# 3_Cambridge_Measurement_TOP.net
KiCad netlist of a schematic drawn in Altium Designer
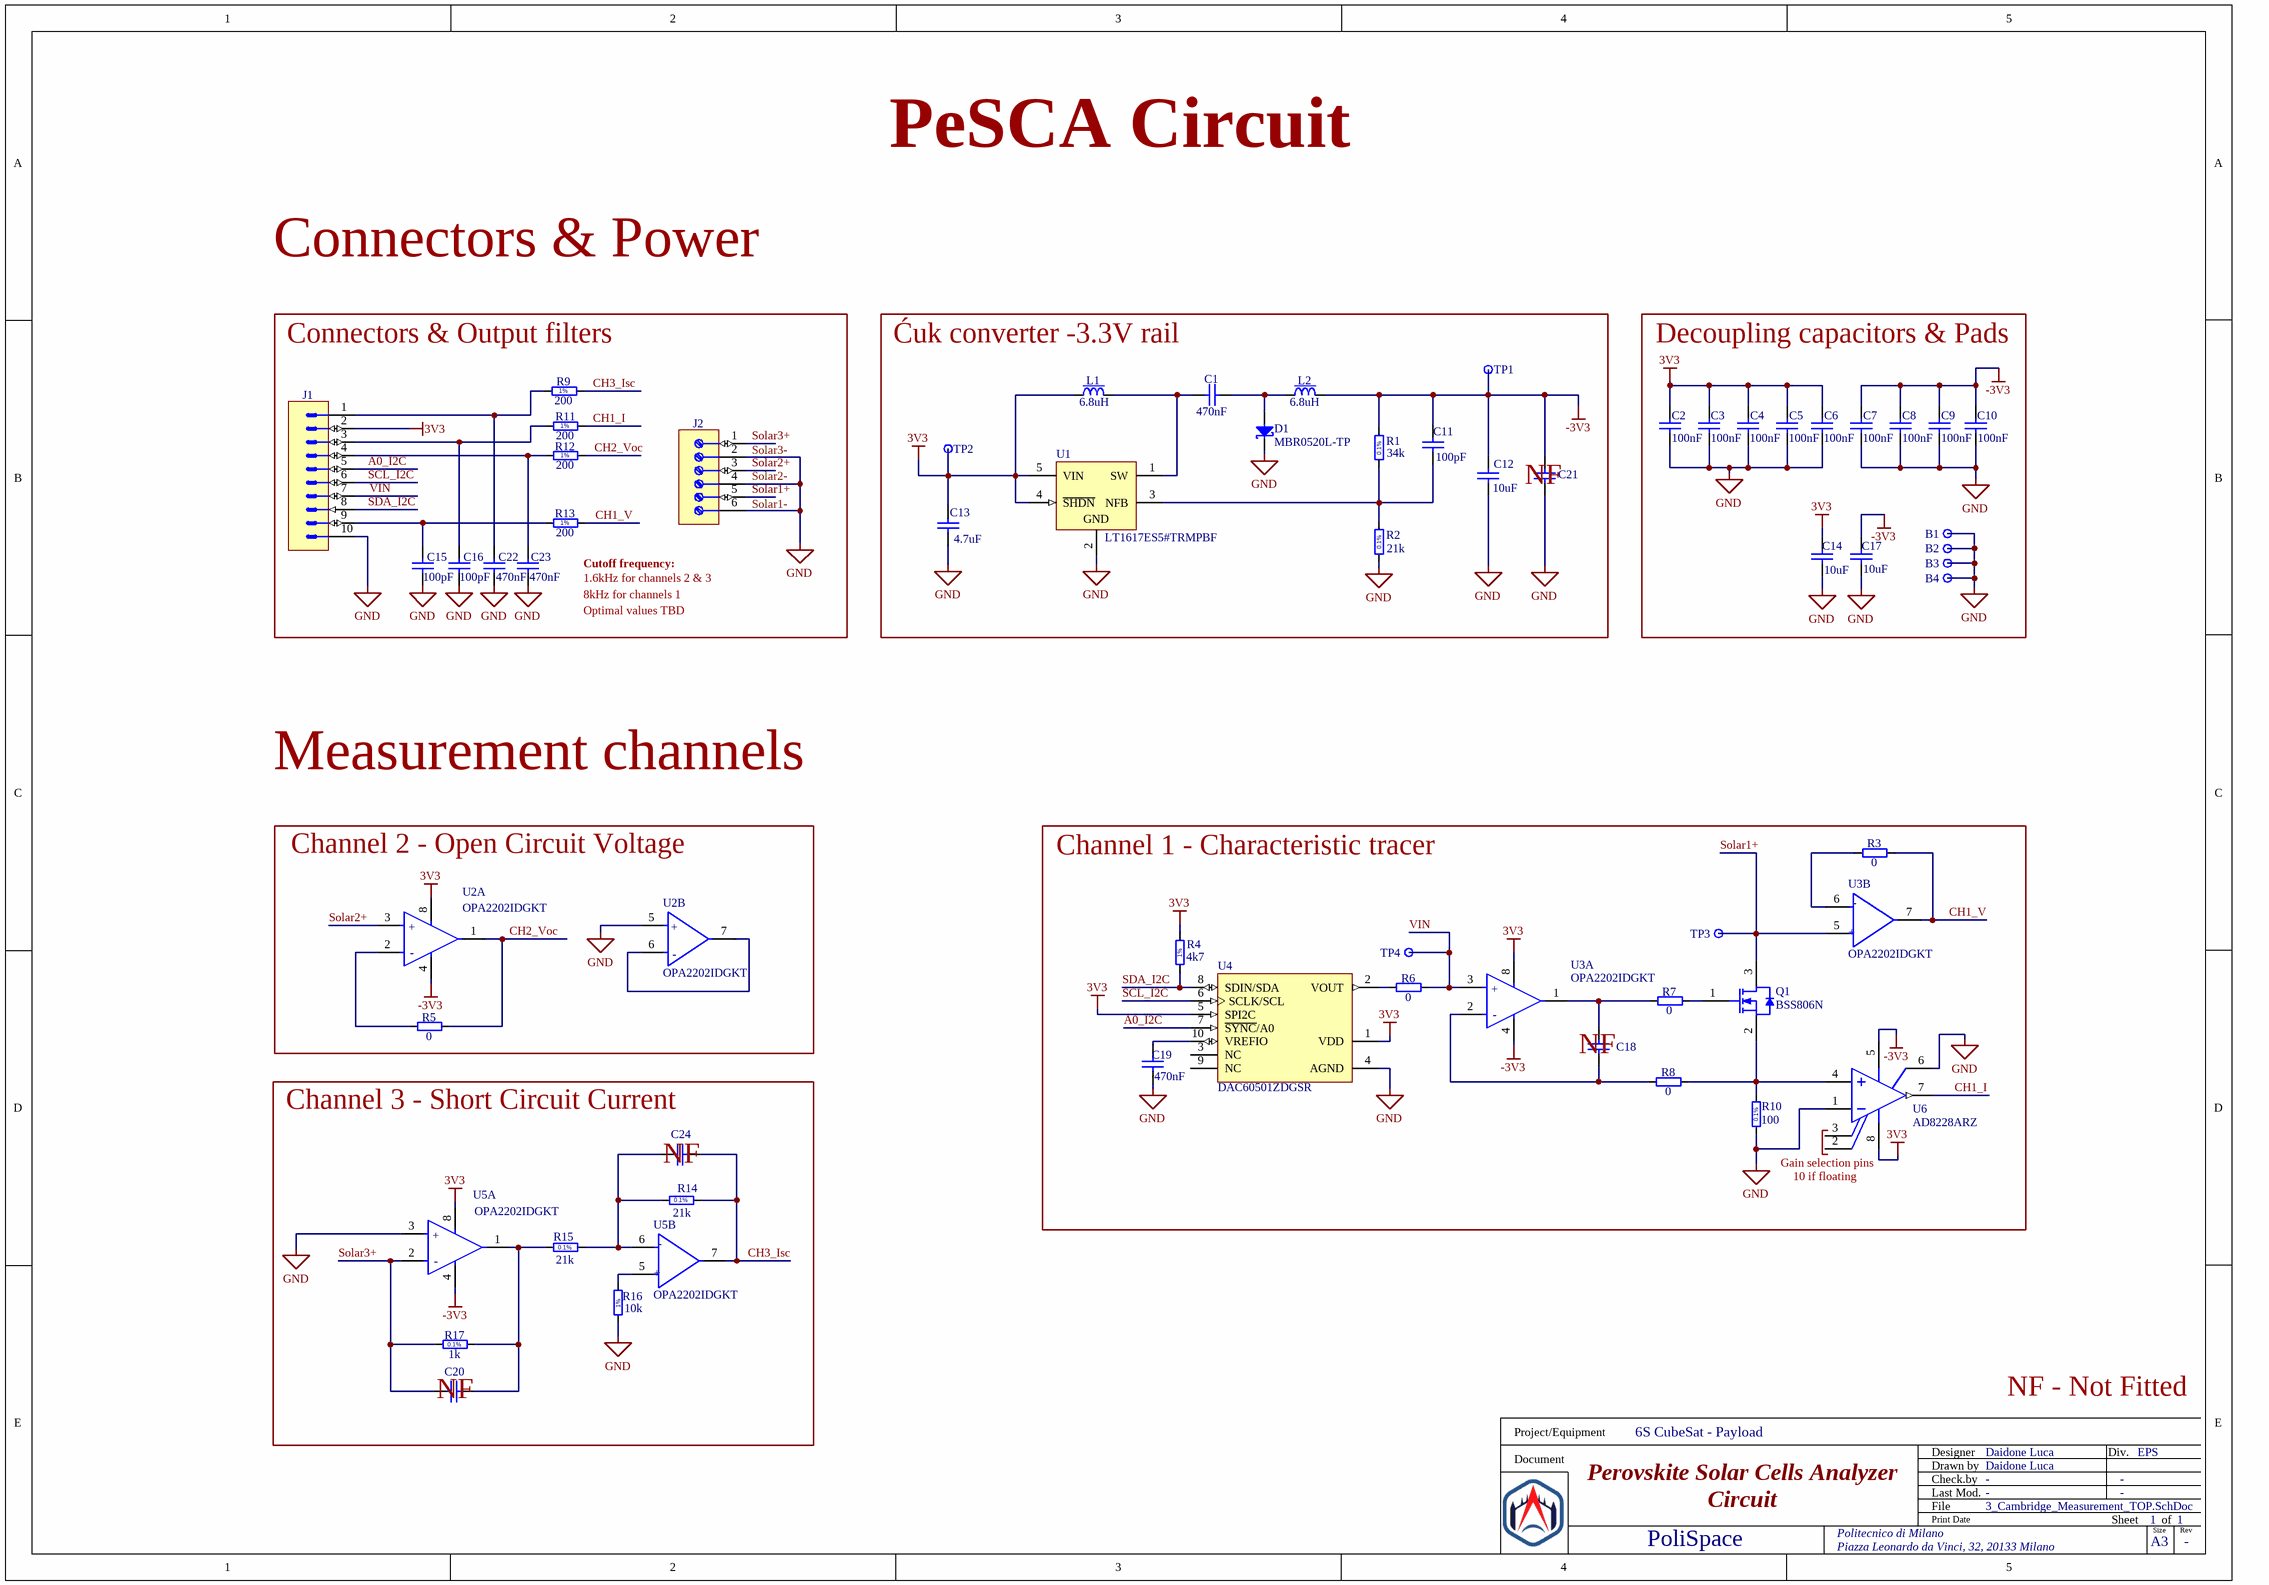
[diagram p0: 3_Cambridge_Measurement_TOP.SchDoc]

(export (version "E")
  (design (tool "Eeschema 10.0.6"))
  (components
    (comp (ref "B1")
      (value "Plated Hole")
      (footprint "MTG350_650")
      (description "Single Terminal Socket")
      (fields (field (name "PART NUMBER") "PLATED_HOLE3.5_PAD6.5") (field (name "AUTHOR") "CERN DEM JLC"))
      (libsource (lib "Eletro-mechanical") (part "Single Terminal Socket"))
    )
    (comp (ref "B2")
      (value "Plated Hole")
      (footprint "MTG350_650")
      (description "Single Terminal Socket")
      (fields (field (name "PART NUMBER") "PLATED_HOLE3.5_PAD6.5") (field (name "AUTHOR") "CERN DEM JLC"))
      (libsource (lib "Eletro-mechanical") (part "Single Terminal Socket"))
    )
    (comp (ref "B3")
      (value "Plated Hole")
      (footprint "MTG350_650")
      (description "Single Terminal Socket")
      (fields (field (name "PART NUMBER") "PLATED_HOLE3.5_PAD6.5") (field (name "AUTHOR") "CERN DEM JLC"))
      (libsource (lib "Eletro-mechanical") (part "Single Terminal Socket"))
    )
    (comp (ref "B4")
      (value "Plated Hole")
      (footprint "MTG350_650")
      (description "Single Terminal Socket")
      (fields (field (name "PART NUMBER") "PLATED_HOLE3.5_PAD6.5") (field (name "AUTHOR") "CERN DEM JLC"))
      (libsource (lib "Eletro-mechanical") (part "Single Terminal Socket"))
    )
    (comp (ref "C1")
      (value "470nF")
      (footprint "CAPC1608X87N")
      (description "Non-polarised capacitor")
      (fields
        (field (name "PART NUMBER") "CC0603_470NF_50V_10%_X5R")
        (field (name "VOLTAGE") "50V")
        (field (name "AUTHOR") "CERN DEM MR")
      )
      (libsource (lib "Capacitors") (part "Capacitor - non polarized"))
    )
    (comp (ref "C2")
      (value "100nF")
      (footprint "CAPC1608X87N")
      (description "Non-polarised capacitor")
      (fields
        (field (name "PART NUMBER") "CC0603_100NF_50V_10%_X7R")
        (field (name "VOLTAGE") "50V")
        (field (name "AUTHOR") "CERN DEM JLC")
      )
      (libsource (lib "Capacitors") (part "Capacitor - non polarized"))
    )
    (comp (ref "C3")
      (value "100nF")
      (footprint "CAPC1608X87N")
      (description "Non-polarised capacitor")
      (fields
        (field (name "PART NUMBER") "CC0603_100NF_50V_10%_X7R")
        (field (name "VOLTAGE") "50V")
        (field (name "AUTHOR") "CERN DEM JLC")
      )
      (libsource (lib "Capacitors") (part "Capacitor - non polarized"))
    )
    (comp (ref "C4")
      (value "100nF")
      (footprint "CAPC1608X87N")
      (description "Non-polarised capacitor")
      (fields
        (field (name "PART NUMBER") "CC0603_100NF_50V_10%_X7R")
        (field (name "VOLTAGE") "50V")
        (field (name "AUTHOR") "CERN DEM JLC")
      )
      (libsource (lib "Capacitors") (part "Capacitor - non polarized"))
    )
    (comp (ref "C5")
      (value "100nF")
      (footprint "CAPC1608X87N")
      (description "Non-polarised capacitor")
      (fields
        (field (name "PART NUMBER") "CC0603_100NF_50V_10%_X7R")
        (field (name "VOLTAGE") "50V")
        (field (name "AUTHOR") "CERN DEM JLC")
      )
      (libsource (lib "Capacitors") (part "Capacitor - non polarized"))
    )
    (comp (ref "C6")
      (value "100nF")
      (footprint "CAPC1608X87N")
      (description "Non-polarised capacitor")
      (fields
        (field (name "PART NUMBER") "CC0603_100NF_50V_10%_X7R")
        (field (name "VOLTAGE") "50V")
        (field (name "AUTHOR") "CERN DEM JLC")
      )
      (libsource (lib "Capacitors") (part "Capacitor - non polarized"))
    )
    (comp (ref "C7")
      (value "100nF")
      (footprint "CAPC1608X87N")
      (description "Non-polarised capacitor")
      (fields
        (field (name "PART NUMBER") "CC0603_100NF_50V_10%_X7R")
        (field (name "VOLTAGE") "50V")
        (field (name "AUTHOR") "CERN DEM JLC")
      )
      (libsource (lib "Capacitors") (part "Capacitor - non polarized"))
    )
    (comp (ref "C8")
      (value "100nF")
      (footprint "CAPC1608X87N")
      (description "Non-polarised capacitor")
      (fields
        (field (name "PART NUMBER") "CC0603_100NF_50V_10%_X7R")
        (field (name "VOLTAGE") "50V")
        (field (name "AUTHOR") "CERN DEM JLC")
      )
      (libsource (lib "Capacitors") (part "Capacitor - non polarized"))
    )
    (comp (ref "C9")
      (value "100nF")
      (footprint "CAPC1608X87N")
      (description "Non-polarised capacitor")
      (fields
        (field (name "PART NUMBER") "CC0603_100NF_50V_10%_X7R")
        (field (name "VOLTAGE") "50V")
        (field (name "AUTHOR") "CERN DEM JLC")
      )
      (libsource (lib "Capacitors") (part "Capacitor - non polarized"))
    )
    (comp (ref "C10")
      (value "100nF")
      (footprint "CAPC1608X87N")
      (description "Non-polarised capacitor")
      (fields
        (field (name "PART NUMBER") "CC0603_100NF_50V_10%_X7R")
        (field (name "VOLTAGE") "50V")
        (field (name "AUTHOR") "CERN DEM JLC")
      )
      (libsource (lib "Capacitors") (part "Capacitor - non polarized"))
    )
    (comp (ref "C11")
      (value "100pF")
      (footprint "CAPC1608X87N")
      (description "Non-polarised capacitor")
      (fields
        (field (name "PART NUMBER") "CC0603_100PF_50V_10%_X7R")
        (field (name "VOLTAGE") "50V")
        (field (name "AUTHOR") "CERN DEM JLC")
      )
      (libsource (lib "Capacitors") (part "Capacitor - non polarized"))
    )
    (comp (ref "C12")
      (value "10uF")
      (footprint "CAPC1608X80N")
      (description "Non-polarised capacitor")
      (fields
        (field (name "PART NUMBER") "CC0603_10UF_16V_20%_X5R")
        (field (name "VOLTAGE") "16V")
        (field (name "AUTHOR") "CERN DEM MR")
      )
      (libsource (lib "Capacitors") (part "Capacitor - non polarized"))
    )
    (comp (ref "C13")
      (value "4.7uF")
      (footprint "CAPC1709X95N")
      (description "Non-polarised capacitor")
      (fields
        (field (name "PART NUMBER") "CC0603_4.7UF_16V_10%_X5R")
        (field (name "VOLTAGE") "16V")
        (field (name "AUTHOR") "CERN DEM JLC")
      )
      (libsource (lib "Capacitors") (part "Capacitor - non polarized"))
    )
    (comp (ref "C14")
      (value "10uF")
      (footprint "CAPC1608X80N")
      (description "Non-polarised capacitor")
      (fields
        (field (name "PART NUMBER") "CC0603_10UF_16V_20%_X5R")
        (field (name "VOLTAGE") "16V")
        (field (name "AUTHOR") "CERN DEM MR")
      )
      (libsource (lib "Capacitors") (part "Capacitor - non polarized"))
    )
    (comp (ref "C15")
      (value "100pF")
      (footprint "CAPC1608X87N")
      (description "Non-polarised capacitor")
      (fields
        (field (name "PART NUMBER") "CC0603_100PF_50V_10%_X7R")
        (field (name "VOLTAGE") "50V")
        (field (name "AUTHOR") "CERN DEM JLC")
      )
      (libsource (lib "Capacitors") (part "Capacitor - non polarized"))
    )
    (comp (ref "C16")
      (value "100pF")
      (footprint "CAPC1608X87N")
      (description "Non-polarised capacitor")
      (fields
        (field (name "PART NUMBER") "CC0603_100PF_50V_10%_X7R")
        (field (name "VOLTAGE") "50V")
        (field (name "AUTHOR") "CERN DEM JLC")
      )
      (libsource (lib "Capacitors") (part "Capacitor - non polarized"))
    )
    (comp (ref "C17")
      (value "10uF")
      (footprint "CAPC1608X80N")
      (description "Non-polarised capacitor")
      (fields
        (field (name "PART NUMBER") "CC0603_10UF_16V_20%_X5R")
        (field (name "VOLTAGE") "16V")
        (field (name "AUTHOR") "CERN DEM MR")
      )
      (libsource (lib "Capacitors") (part "Capacitor - non polarized"))
    )
    (comp (ref "C18")
      (value "100nF")
      (footprint "CAPC1608X87N")
      (description "Non-polarised capacitor")
      (fields
        (field (name "PART NUMBER") "CC0603_100NF_50V_10%_X7R")
        (field (name "VOLTAGE") "50V")
        (field (name "AUTHOR") "CERN DEM JLC")
      )
      (libsource (lib "Capacitors") (part "Capacitor - non polarized"))
    )
    (comp (ref "C19")
      (value "470nF")
      (footprint "CAPC1608X87N")
      (description "Non-polarised capacitor")
      (fields
        (field (name "PART NUMBER") "CC0603_470NF_50V_10%_X5R")
        (field (name "VOLTAGE") "50V")
        (field (name "AUTHOR") "CERN DEM MR")
      )
      (libsource (lib "Capacitors") (part "Capacitor - non polarized"))
    )
    (comp (ref "C20")
      (value "100nF")
      (footprint "CAPC1608X87N")
      (description "Non-polarised capacitor")
      (fields
        (field (name "PART NUMBER") "CC0603_100NF_50V_10%_X7R")
        (field (name "VOLTAGE") "50V")
        (field (name "AUTHOR") "CERN DEM JLC")
      )
      (libsource (lib "Capacitors") (part "Capacitor - non polarized"))
    )
    (comp (ref "C21")
      (value "10uF")
      (footprint "CAPC2012X135N")
      (description "Non-polarised capacitor")
      (fields
        (field (name "PART NUMBER") "CC0805_10UF_16V_10%_X5R")
        (field (name "VOLTAGE") "16V")
        (field (name "AUTHOR") "CERN DEM JLC")
      )
      (libsource (lib "Capacitors") (part "Capacitor - non polarized"))
    )
    (comp (ref "C22")
      (value "470nF")
      (footprint "CAPC1608X87N")
      (description "Non-polarised capacitor")
      (fields
        (field (name "PART NUMBER") "CC0603_470NF_50V_10%_X5R")
        (field (name "VOLTAGE") "50V")
        (field (name "AUTHOR") "CERN DEM MR")
      )
      (libsource (lib "Capacitors") (part "Capacitor - non polarized"))
    )
    (comp (ref "C23")
      (value "470nF")
      (footprint "CAPC1608X87N")
      (description "Non-polarised capacitor")
      (fields
        (field (name "PART NUMBER") "CC0603_470NF_50V_10%_X5R")
        (field (name "VOLTAGE") "50V")
        (field (name "AUTHOR") "CERN DEM MR")
      )
      (libsource (lib "Capacitors") (part "Capacitor - non polarized"))
    )
    (comp (ref "C24")
      (value "100nF")
      (footprint "CAPC1608X87N")
      (description "Non-polarised capacitor")
      (fields
        (field (name "PART NUMBER") "CC0603_100NF_50V_10%_X7R")
        (field (name "VOLTAGE") "50V")
        (field (name "AUTHOR") "CERN DEM JLC")
      )
      (libsource (lib "Capacitors") (part "Capacitor - non polarized"))
    )
    (comp (ref "D1")
      (value "MBR0520L-TP")
      (footprint "SOD3715X135N")
      (description "Diode Schottky 20V 0.5A 2-Pin SOD-123 T/R")
      (fields (field (name "MANUFACTURER") "MCC") (field (name "MANUFACTURER PART NUMBER") "MBR0520-TP"))
      (libsource (lib "6SCubeSat") (part "MBR0520L-TP"))
    )
    (comp (ref "J1")
      (value "Header 10")
      (footprint "HARWIN_M20-9980546")
      (description "Connector 10 Male")
      (fields
        (field (name "PART NUMBER") "HARWIN_M20-9980546")
        (field (name "MANUFACTURER") "HARWIN")
        (field (name "AUTHOR") "CERN DEM MR")
      )
      (libsource (lib "Connectors") (part "Connector 10 Male"))
    )
    (comp (ref "J2")
      (value "~")
      (footprint "PHOENIX_1725698")
      (description "Terminal Block, 6 Positions, Screw Connection")
      (fields
        (field (name "PART NUMBER") "PHOENIX_1725698")
        (field (name "MANUFACTURER") "PHOENIX CONTACT")
        (field (name "AUTHOR") "CERN DEM JMW")
      )
      (libsource (lib "Connectors") (part "Terminal Block_6 Positions_Screw Connection"))
    )
    (comp (ref "L1")
      (value "6.8uH")
      (footprint "IND_TDK_VLCF5020-1")
      (description "Inductor With Core")
      (fields
        (field (name "PART NUMBER") "IND_10UH_20%_TDK_VLCF5020-1")
        (field (name "POWER") "1.5A")
        (field (name "AUTHOR") "CERN DEM JLC")
      )
      (libsource (lib "Inductors & Transformers") (part "Inductor With Magnetic core"))
    )
    (comp (ref "L2")
      (value "6.8uH")
      (footprint "IND_TDK_VLCF5020-1")
      (description "Inductor With Core")
      (fields
        (field (name "PART NUMBER") "IND_10UH_20%_TDK_VLCF5020-1")
        (field (name "POWER") "1.5A")
        (field (name "AUTHOR") "CERN DEM JLC")
      )
      (libsource (lib "Inductors & Transformers") (part "Inductor With Magnetic core"))
    )
    (comp (ref "Q1")
      (value "BSS806N")
      (footprint "INF-PG-SOT23_M")
      (fields (field (name "MANUFACTURER") "Infineon"))
      (libsource (lib "Altium Content Vault") (part "INF-NEMOS-GSD-3"))
    )
    (comp (ref "R1")
      (value "34k")
      (footprint "RESC1608X55N")
      (description "Resistor - 0.1%")
      (fields
        (field (name "PART NUMBER") "R0603_34K_0.1%_0.063W_10PPM")
        (field (name "POWER") "0.063W")
        (field (name "AUTHOR") "CERN DEM JLC")
      )
      (libsource (lib "Resistors") (part "Resistor - 0.1%"))
    )
    (comp (ref "R2")
      (value "21k")
      (footprint "RESC1608X55N")
      (description "Resistor - 0.1%")
      (fields
        (field (name "PART NUMBER") "R0603_21K_0.1%_0.063W_10PPM")
        (field (name "POWER") "0.063W")
        (field (name "AUTHOR") "CERN DEM JLC")
      )
      (libsource (lib "Resistors") (part "Resistor - 0.1%"))
    )
    (comp (ref "R3")
      (value "0")
      (footprint "RESC1608X55N")
      (description "Resistor")
      (fields
        (field (name "PART NUMBER") "R0603_0R_JUMPER")
        (field (name "MANUFACTURER") "GENERIC")
        (field (name "AUTHOR") "CERN DEM JLC")
      )
      (libsource (lib "Resistors") (part "Resistor"))
    )
    (comp (ref "R4")
      (value "4k7")
      (footprint "RESC1608X55N")
      (description "Resistor - 1%")
      (fields
        (field (name "PART NUMBER") "R0603_4K7_1%_0.1W_100PPM")
        (field (name "POWER") "0.1W")
        (field (name "AUTHOR") "CERN DEM JLC")
      )
      (libsource (lib "Resistors") (part "Resistor - 1%"))
    )
    (comp (ref "R5")
      (value "0")
      (footprint "RESC1608X55N")
      (description "Resistor")
      (fields
        (field (name "PART NUMBER") "R0603_0R_JUMPER")
        (field (name "MANUFACTURER") "GENERIC")
        (field (name "AUTHOR") "CERN DEM JLC")
      )
      (libsource (lib "Resistors") (part "Resistor"))
    )
    (comp (ref "R6")
      (value "0")
      (footprint "RESC1608X55N")
      (description "Resistor")
      (fields
        (field (name "PART NUMBER") "R0603_0R_JUMPER")
        (field (name "MANUFACTURER") "GENERIC")
        (field (name "AUTHOR") "CERN DEM JLC")
      )
      (libsource (lib "Resistors") (part "Resistor"))
    )
    (comp (ref "R7")
      (value "0")
      (footprint "RESC1608X55N")
      (description "Resistor")
      (fields
        (field (name "PART NUMBER") "R0603_0R_JUMPER")
        (field (name "MANUFACTURER") "GENERIC")
        (field (name "AUTHOR") "CERN DEM JLC")
      )
      (libsource (lib "Resistors") (part "Resistor"))
    )
    (comp (ref "R8")
      (value "0")
      (footprint "RESC1608X55N")
      (description "Resistor")
      (fields
        (field (name "PART NUMBER") "R0603_0R_JUMPER")
        (field (name "MANUFACTURER") "GENERIC")
        (field (name "AUTHOR") "CERN DEM JLC")
      )
      (libsource (lib "Resistors") (part "Resistor"))
    )
    (comp (ref "R9")
      (value "200")
      (footprint "RESC1608X55N")
      (description "Resistor - 1%")
      (fields
        (field (name "PART NUMBER") "R0603_200R_1%_0.1W_100PPM")
        (field (name "POWER") "0.1W")
        (field (name "AUTHOR") "CERN DEM JLC")
      )
      (libsource (lib "Resistors") (part "Resistor - 1%"))
    )
    (comp (ref "R10")
      (value "100")
      (footprint "RESC1608X55N")
      (description "Resistor - 0.1%")
      (fields
        (field (name "PART NUMBER") "R0603_100R_0.1%_0.063W_10PPM")
        (field (name "POWER") "0.063W")
        (field (name "AUTHOR") "CERN DEM JLC")
      )
      (libsource (lib "Resistors") (part "Resistor - 0.1%"))
    )
    (comp (ref "R11")
      (value "200")
      (footprint "RESC1608X55N")
      (description "Resistor - 1%")
      (fields
        (field (name "PART NUMBER") "R0603_200R_1%_0.1W_100PPM")
        (field (name "POWER") "0.1W")
        (field (name "AUTHOR") "CERN DEM JLC")
      )
      (libsource (lib "Resistors") (part "Resistor - 1%"))
    )
    (comp (ref "R12")
      (value "200")
      (footprint "RESC1608X55N")
      (description "Resistor - 1%")
      (fields
        (field (name "PART NUMBER") "R0603_200R_1%_0.1W_100PPM")
        (field (name "POWER") "0.1W")
        (field (name "AUTHOR") "CERN DEM JLC")
      )
      (libsource (lib "Resistors") (part "Resistor - 1%"))
    )
    (comp (ref "R13")
      (value "200")
      (footprint "RESC1608X55N")
      (description "Resistor - 1%")
      (fields
        (field (name "PART NUMBER") "R0603_200R_1%_0.1W_100PPM")
        (field (name "POWER") "0.1W")
        (field (name "AUTHOR") "CERN DEM JLC")
      )
      (libsource (lib "Resistors") (part "Resistor - 1%"))
    )
    (comp (ref "R14")
      (value "21k")
      (footprint "RESC1608X55N")
      (description "Resistor - 0.1%")
      (fields
        (field (name "PART NUMBER") "R0603_21K_0.1%_0.063W_10PPM")
        (field (name "POWER") "0.063W")
        (field (name "AUTHOR") "CERN DEM JLC")
      )
      (libsource (lib "Resistors") (part "Resistor - 0.1%"))
    )
    (comp (ref "R15")
      (value "21k")
      (footprint "RESC1608X55N")
      (description "Resistor - 0.1%")
      (fields
        (field (name "PART NUMBER") "R0603_21K_0.1%_0.063W_10PPM")
        (field (name "POWER") "0.063W")
        (field (name "AUTHOR") "CERN DEM JLC")
      )
      (libsource (lib "Resistors") (part "Resistor - 0.1%"))
    )
    (comp (ref "R16")
      (value "10k")
      (footprint "RESC1608X55N")
      (description "Resistor - 1%")
      (fields
        (field (name "PART NUMBER") "R0603_10K_1%_0.1W_100PPM")
        (field (name "POWER") "0.1W")
        (field (name "AUTHOR") "CERN DEM JLC")
      )
      (libsource (lib "Resistors") (part "Resistor - 1%"))
    )
    (comp (ref "R17")
      (value "1k")
      (footprint "RESC1608X55N")
      (description "Resistor - 0.1%")
      (fields
        (field (name "PART NUMBER") "R0603_1K_0.1%_0.063W_10PPM")
        (field (name "POWER") "0.063W")
        (field (name "AUTHOR") "CERN DEM BC")
      )
      (libsource (lib "Resistors") (part "Resistor - 0.1%"))
    )
    (comp (ref "TP1")
      (value "Test Point")
      (footprint "TPS127")
      (fields (field (name "PART NUMBER") "SMD_PAD_1.27X1.27MM") (field (name "AUTHOR") "CERN DEM JLC"))
      (libsource (lib "Eletro-mechanical") (part "Test Point"))
    )
    (comp (ref "TP2")
      (value "Test Point")
      (footprint "TPS127")
      (fields (field (name "PART NUMBER") "SMD_PAD_1.27X1.27MM") (field (name "AUTHOR") "CERN DEM JLC"))
      (libsource (lib "Eletro-mechanical") (part "Test Point"))
    )
    (comp (ref "TP3")
      (value "Test Point")
      (footprint "TPS127")
      (fields (field (name "PART NUMBER") "SMD_PAD_1.27X1.27MM") (field (name "AUTHOR") "CERN DEM JLC"))
      (libsource (lib "Eletro-mechanical") (part "Test Point"))
    )
    (comp (ref "TP4")
      (value "Test Point")
      (footprint "TPS127")
      (fields (field (name "PART NUMBER") "SMD_PAD_1.27X1.27MM") (field (name "AUTHOR") "CERN DEM JLC"))
      (libsource (lib "Eletro-mechanical") (part "Test Point"))
    )
    (comp (ref "U1")
      (value "LT1617ES5#TRMPBF")
      (footprint "LT-S5-5-SOT-23_L")
      (fields (field (name "MANUFACTURER") "Linear Technology"))
      (libsource (lib "Altium Content Vault") (part "LT-LT161X_1931-S5-5"))
    )
    (comp (ref "U2")
      (value "OPA2202IDGKT")
      (footprint "FP-DGK0008A-IPC_A")
      (description "IC OPAMP GP 2 CIRCUIT 8VSSOP")
      (libsource (lib "Altium Content Vault") (part "499df5fc91ff7ad023bcaf249d8becd"))
    )
    (comp (ref "U3")
      (value "OPA2202IDGKT")
      (footprint "FP-DGK0008A-IPC_A")
      (description "IC OPAMP GP 2 CIRCUIT 8VSSOP")
      (libsource (lib "Altium Content Vault") (part "499df5fc91ff7ad023bcaf249d8becd"))
    )
    (comp (ref "U4")
      (value "DAC60501ZDGSR")
      (footprint "SOP50P490X110-10N")
      (description "12-Bit Voltage Output DAC with Precision Internal Reference 1-LSB INL 10-Pin VSSOP T/R")
      (fields (field (name "MANUFACTURER") "Texas Instruments"))
      (libsource (lib "6SCubeSat") (part "DAC60501ZDGSR"))
    )
    (comp (ref "U5")
      (value "OPA2202IDGKT")
      (footprint "FP-DGK0008A-IPC_A")
      (description "IC OPAMP GP 2 CIRCUIT 8VSSOP")
      (libsource (lib "Altium Content Vault") (part "499df5fc91ff7ad023bcaf249d8becd"))
    )
    (comp (ref "U6")
      (value "AD8228ARZ")
      (footprint "ADI-R-8_L")
      (fields (field (name "MANUFACTURER") "Analog Devices"))
      (libsource (lib "Altium Content Vault") (part "ADI-AD8228-8"))
    )
  )
  (nets
    (net (code "1") (name "-3V3") (class "Default")
      (node (ref "C10") (pin "2") (pinfunction "2_2") (pintype "passive"))
      (node (ref "C11") (pin "2") (pinfunction "2_2") (pintype "passive"))
      (node (ref "C12") (pin "2") (pinfunction "2_2") (pintype "passive"))
      (node (ref "C17") (pin "2") (pinfunction "2_2") (pintype "passive"))
      (node (ref "C21") (pin "2") (pinfunction "2_2") (pintype "passive"))
      (node (ref "C7") (pin "2") (pinfunction "2_2") (pintype "passive"))
      (node (ref "C8") (pin "2") (pinfunction "2_2") (pintype "passive"))
      (node (ref "C9") (pin "2") (pinfunction "2_2") (pintype "passive"))
      (node (ref "L2") (pin "2") (pinfunction "2_2") (pintype "passive"))
      (node (ref "R1") (pin "2") (pinfunction "2_2") (pintype "passive"))
      (node (ref "TP1") (pin "1") (pinfunction "1_1") (pintype "bidirectional"))
      (node (ref "U2") (pin "4") (pinfunction "V-_4") (pintype "power_in"))
      (node (ref "U3") (pin "4") (pinfunction "V-_4") (pintype "power_in"))
      (node (ref "U5") (pin "4") (pinfunction "V-_4") (pintype "power_in"))
      (node (ref "U6") (pin "5") (pinfunction "VS-_5") (pintype "power_in"))
    )
    (net (code "2") (name "/A0_I2C") (class "Default")
      (node (ref "J1") (pin "5") (pinfunction "5_5") (pintype "bidirectional"))
      (node (ref "U4") (pin "7") (pinfunction "~{SYNC}/A0_7") (pintype "input"))
    )
    (net (code "3") (name "/CH1_I") (class "Default")
      (node (ref "R11") (pin "2") (pinfunction "2_2") (pintype "passive"))
      (node (ref "U6") (pin "7") (pinfunction "VOUT_7") (pintype "output"))
    )
    (net (code "4") (name "/CH1_V") (class "Default")
      (node (ref "R13") (pin "2") (pinfunction "2_2") (pintype "passive"))
      (node (ref "R3") (pin "2") (pinfunction "2_2") (pintype "passive"))
      (node (ref "U3") (pin "7") (pinfunction "OUT_B_7") (pintype "passive"))
    )
    (net (code "5") (name "/CH2_Voc") (class "Default")
      (node (ref "R12") (pin "2") (pinfunction "2_2") (pintype "passive"))
      (node (ref "R5") (pin "2") (pinfunction "2_2") (pintype "passive"))
      (node (ref "U2") (pin "1") (pinfunction "OUT_A_1") (pintype "passive"))
    )
    (net (code "6") (name "/CH3_Isc") (class "Default")
      (node (ref "C24") (pin "1") (pinfunction "1_1") (pintype "passive"))
      (node (ref "R14") (pin "2") (pinfunction "2_2") (pintype "passive"))
      (node (ref "R9") (pin "2") (pinfunction "2_2") (pintype "passive"))
      (node (ref "U5") (pin "7") (pinfunction "OUT_B_7") (pintype "passive"))
    )
    (net (code "7") (name "/SCL_I2C") (class "Default")
      (node (ref "J1") (pin "6") (pinfunction "6_6") (pintype "bidirectional"))
      (node (ref "U4") (pin "6") (pinfunction "SCLK/SCL_6") (pintype "input"))
    )
    (net (code "8") (name "/SDA_I2C") (class "Default")
      (node (ref "J1") (pin "8") (pinfunction "8_8") (pintype "input"))
      (node (ref "R4") (pin "1") (pinfunction "1_1") (pintype "passive"))
      (node (ref "U4") (pin "8") (pinfunction "SDIN/SDA_8") (pintype "bidirectional"))
    )
    (net (code "9") (name "/Solar1+") (class "Default")
      (node (ref "J2") (pin "5") (pinfunction "5_5") (pintype "bidirectional"))
      (node (ref "Q1") (pin "3") (pinfunction "DRAIN_3") (pintype "passive"))
      (node (ref "TP3") (pin "1") (pinfunction "1_1") (pintype "bidirectional"))
      (node (ref "U3") (pin "5") (pinfunction "+IN_B_5") (pintype "tri_state"))
    )
    (net (code "10") (name "/Solar2+") (class "Default")
      (node (ref "J2") (pin "3") (pinfunction "3_3") (pintype "bidirectional"))
      (node (ref "U2") (pin "3") (pinfunction "+IN_A_3") (pintype "tri_state"))
    )
    (net (code "11") (name "/Solar3+") (class "Default")
      (node (ref "C20") (pin "2") (pinfunction "2_2") (pintype "passive"))
      (node (ref "J2") (pin "1") (pinfunction "1_1") (pintype "bidirectional"))
      (node (ref "R17") (pin "1") (pinfunction "1_1") (pintype "passive"))
      (node (ref "U5") (pin "2") (pinfunction "-IN_A_2") (pintype "tri_state"))
    )
    (net (code "12") (name "/VIN") (class "Default")
      (node (ref "J1") (pin "7") (pinfunction "7_7") (pintype "bidirectional"))
      (node (ref "R6") (pin "2") (pinfunction "2_2") (pintype "passive"))
      (node (ref "TP4") (pin "1") (pinfunction "1_1") (pintype "bidirectional"))
      (node (ref "U3") (pin "3") (pinfunction "+IN_A_3") (pintype "tri_state"))
    )
    (net (code "13") (name "3V3") (class "Default")
      (node (ref "C13") (pin "2") (pinfunction "2_2") (pintype "passive"))
      (node (ref "C14") (pin "2") (pinfunction "2_2") (pintype "passive"))
      (node (ref "C2") (pin "2") (pinfunction "2_2") (pintype "passive"))
      (node (ref "C3") (pin "2") (pinfunction "2_2") (pintype "passive"))
      (node (ref "C4") (pin "2") (pinfunction "2_2") (pintype "passive"))
      (node (ref "C5") (pin "2") (pinfunction "2_2") (pintype "passive"))
      (node (ref "C6") (pin "2") (pinfunction "2_2") (pintype "passive"))
      (node (ref "J1") (pin "2") (pinfunction "2_2") (pintype "bidirectional"))
      (node (ref "L1") (pin "1") (pinfunction "1_1") (pintype "passive"))
      (node (ref "R4") (pin "2") (pinfunction "2_2") (pintype "passive"))
      (node (ref "TP2") (pin "1") (pinfunction "1_1") (pintype "bidirectional"))
      (node (ref "U1") (pin "4") (pinfunction "~{SHDN}_4") (pintype "input"))
      (node (ref "U1") (pin "5") (pinfunction "VIN_5") (pintype "power_in"))
      (node (ref "U2") (pin "8") (pinfunction "V+_8") (pintype "power_in"))
      (node (ref "U3") (pin "8") (pinfunction "V+_8") (pintype "power_in"))
      (node (ref "U4") (pin "1") (pinfunction "VDD_1") (pintype "power_in"))
      (node (ref "U4") (pin "5") (pinfunction "SPI2C_5") (pintype "input"))
      (node (ref "U5") (pin "8") (pinfunction "V+_8") (pintype "power_in"))
      (node (ref "U6") (pin "8") (pinfunction "VS+_8") (pintype "power_in"))
    )
    (net (code "14") (name "GND") (class "Default")
      (node (ref "B1") (pin "1") (pinfunction "1_1") (pintype "bidirectional"))
      (node (ref "B2") (pin "1") (pinfunction "1_1") (pintype "bidirectional"))
      (node (ref "B3") (pin "1") (pinfunction "1_1") (pintype "bidirectional"))
      (node (ref "B4") (pin "1") (pinfunction "1_1") (pintype "bidirectional"))
      (node (ref "C10") (pin "1") (pinfunction "1_1") (pintype "passive"))
      (node (ref "C12") (pin "1") (pinfunction "1_1") (pintype "passive"))
      (node (ref "C13") (pin "1") (pinfunction "1_1") (pintype "passive"))
      (node (ref "C14") (pin "1") (pinfunction "1_1") (pintype "passive"))
      (node (ref "C15") (pin "1") (pinfunction "1_1") (pintype "passive"))
      (node (ref "C16") (pin "1") (pinfunction "1_1") (pintype "passive"))
      (node (ref "C17") (pin "1") (pinfunction "1_1") (pintype "passive"))
      (node (ref "C19") (pin "2") (pinfunction "2_2") (pintype "passive"))
      (node (ref "C2") (pin "1") (pinfunction "1_1") (pintype "passive"))
      (node (ref "C21") (pin "1") (pinfunction "1_1") (pintype "passive"))
      (node (ref "C22") (pin "1") (pinfunction "1_1") (pintype "passive"))
      (node (ref "C23") (pin "1") (pinfunction "1_1") (pintype "passive"))
      (node (ref "C3") (pin "1") (pinfunction "1_1") (pintype "passive"))
      (node (ref "C4") (pin "1") (pinfunction "1_1") (pintype "passive"))
      (node (ref "C5") (pin "1") (pinfunction "1_1") (pintype "passive"))
      (node (ref "C6") (pin "1") (pinfunction "1_1") (pintype "passive"))
      (node (ref "C7") (pin "1") (pinfunction "1_1") (pintype "passive"))
      (node (ref "C8") (pin "1") (pinfunction "1_1") (pintype "passive"))
      (node (ref "C9") (pin "1") (pinfunction "1_1") (pintype "passive"))
      (node (ref "D1") (pin "1") (pinfunction "C_1") (pintype "passive"))
      (node (ref "J1") (pin "10") (pinfunction "10_10") (pintype "power_in"))
      (node (ref "J2") (pin "2") (pinfunction "2_2") (pintype "power_in"))
      (node (ref "J2") (pin "4") (pinfunction "4_4") (pintype "power_in"))
      (node (ref "J2") (pin "6") (pinfunction "6_6") (pintype "power_in"))
      (node (ref "R10") (pin "1") (pinfunction "1_1") (pintype "passive"))
      (node (ref "R16") (pin "1") (pinfunction "1_1") (pintype "passive"))
      (node (ref "R2") (pin "1") (pinfunction "1_1") (pintype "passive"))
      (node (ref "U1") (pin "2") (pinfunction "GND_2") (pintype "power_in"))
      (node (ref "U2") (pin "5") (pinfunction "+IN_B_5") (pintype "tri_state"))
      (node (ref "U4") (pin "4") (pinfunction "AGND_4") (pintype "power_in"))
      (node (ref "U5") (pin "3") (pinfunction "+IN_A_3") (pintype "tri_state"))
      (node (ref "U6") (pin "1") (pinfunction "IN-_1") (pintype "tri_state"))
      (node (ref "U6") (pin "6") (pinfunction "REF_6") (pintype "passive"))
    )
    (net (code "15") (name "Net-(C15-Pad2)") (class "Default")
      (node (ref "C15") (pin "2") (pinfunction "2_2") (pintype "passive"))
      (node (ref "J1") (pin "9") (pinfunction "9_9") (pintype "bidirectional"))
      (node (ref "R13") (pin "1") (pinfunction "1_1") (pintype "passive"))
    )
    (net (code "16") (name "Net-(C16-Pad2)") (class "Default")
      (node (ref "C16") (pin "2") (pinfunction "2_2") (pintype "passive"))
      (node (ref "J1") (pin "3") (pinfunction "3_3") (pintype "bidirectional"))
      (node (ref "R11") (pin "1") (pinfunction "1_1") (pintype "passive"))
    )
    (net (code "17") (name "Net-(C22-Pad2)") (class "Default")
      (node (ref "C22") (pin "2") (pinfunction "2_2") (pintype "passive"))
      (node (ref "J1") (pin "1") (pinfunction "1_1") (pintype "power_in"))
      (node (ref "R9") (pin "1") (pinfunction "1_1") (pintype "passive"))
    )
    (net (code "18") (name "Net-(C23-Pad2)") (class "Default")
      (node (ref "C23") (pin "2") (pinfunction "2_2") (pintype "passive"))
      (node (ref "J1") (pin "4") (pinfunction "4_4") (pintype "bidirectional"))
      (node (ref "R12") (pin "1") (pinfunction "1_1") (pintype "passive"))
    )
    (net (code "19") (name "Net-(D1-A)") (class "Default")
      (node (ref "C1") (pin "2") (pinfunction "2_2") (pintype "passive"))
      (node (ref "D1") (pin "2") (pinfunction "A_2") (pintype "passive"))
      (node (ref "L2") (pin "1") (pinfunction "1_1") (pintype "passive"))
    )
    (net (code "20") (name "Net-(Q1-GATE)") (class "Default")
      (node (ref "Q1") (pin "1") (pinfunction "GATE_1") (pintype "passive"))
      (node (ref "R7") (pin "2") (pinfunction "2_2") (pintype "passive"))
    )
    (net (code "21") (name "Net-(Q1-SOURCE)") (class "Default")
      (node (ref "Q1") (pin "2") (pinfunction "SOURCE_2") (pintype "passive"))
      (node (ref "R10") (pin "2") (pinfunction "2_2") (pintype "passive"))
      (node (ref "R8") (pin "2") (pinfunction "2_2") (pintype "passive"))
      (node (ref "U6") (pin "4") (pinfunction "IN+_4") (pintype "tri_state"))
    )
    (net (code "22") (name "Net-(U1-NFB)") (class "Default")
      (node (ref "C11") (pin "1") (pinfunction "1_1") (pintype "passive"))
      (node (ref "R1") (pin "1") (pinfunction "1_1") (pintype "passive"))
      (node (ref "R2") (pin "2") (pinfunction "2_2") (pintype "passive"))
      (node (ref "U1") (pin "3") (pinfunction "NFB_3") (pintype "tri_state"))
    )
    (net (code "23") (name "Net-(U1-SW)") (class "Default")
      (node (ref "C1") (pin "1") (pinfunction "1_1") (pintype "passive"))
      (node (ref "L1") (pin "2") (pinfunction "2_2") (pintype "passive"))
      (node (ref "U1") (pin "1") (pinfunction "SW_1") (pintype "power_in"))
    )
    (net (code "24") (name "Net-(U2A--IN_A)") (class "Default")
      (node (ref "R5") (pin "1") (pinfunction "1_1") (pintype "passive"))
      (node (ref "U2") (pin "2") (pinfunction "-IN_A_2") (pintype "tri_state"))
    )
    (net (code "25") (name "Net-(U2B--IN_B)") (class "Default")
      (node (ref "U2") (pin "6") (pinfunction "-IN_B_6") (pintype "tri_state"))
      (node (ref "U2") (pin "7") (pinfunction "OUT_B_7") (pintype "passive"))
    )
    (net (code "26") (name "Net-(U3A--IN_A)") (class "Default")
      (node (ref "C18") (pin "1") (pinfunction "1_1") (pintype "passive"))
      (node (ref "R8") (pin "1") (pinfunction "1_1") (pintype "passive"))
      (node (ref "U3") (pin "2") (pinfunction "-IN_A_2") (pintype "tri_state"))
    )
    (net (code "27") (name "Net-(U3A-OUT_A)") (class "Default")
      (node (ref "C18") (pin "2") (pinfunction "2_2") (pintype "passive"))
      (node (ref "R7") (pin "1") (pinfunction "1_1") (pintype "passive"))
      (node (ref "U3") (pin "1") (pinfunction "OUT_A_1") (pintype "passive"))
    )
    (net (code "28") (name "Net-(U3B--IN_B)") (class "Default")
      (node (ref "R3") (pin "1") (pinfunction "1_1") (pintype "passive"))
      (node (ref "U3") (pin "6") (pinfunction "-IN_B_6") (pintype "tri_state"))
    )
    (net (code "29") (name "Net-(U4-VOUT)") (class "Default")
      (node (ref "R6") (pin "1") (pinfunction "1_1") (pintype "passive"))
      (node (ref "U4") (pin "2") (pinfunction "VOUT_2") (pintype "output"))
    )
    (net (code "30") (name "Net-(U4-VREFIO)") (class "Default")
      (node (ref "C19") (pin "1") (pinfunction "1_1") (pintype "passive"))
      (node (ref "U4") (pin "10") (pinfunction "VREFIO_10") (pintype "bidirectional"))
    )
    (net (code "31") (name "Net-(U5A-OUT_A)") (class "Default")
      (node (ref "C20") (pin "1") (pinfunction "1_1") (pintype "passive"))
      (node (ref "R15") (pin "1") (pinfunction "1_1") (pintype "passive"))
      (node (ref "R17") (pin "2") (pinfunction "2_2") (pintype "passive"))
      (node (ref "U5") (pin "1") (pinfunction "OUT_A_1") (pintype "passive"))
    )
    (net (code "32") (name "Net-(U5B-+IN_B)") (class "Default")
      (node (ref "R16") (pin "2") (pinfunction "2_2") (pintype "passive"))
      (node (ref "U5") (pin "5") (pinfunction "+IN_B_5") (pintype "tri_state"))
    )
    (net (code "33") (name "Net-(U5B--IN_B)") (class "Default")
      (node (ref "C24") (pin "2") (pinfunction "2_2") (pintype "passive"))
      (node (ref "R14") (pin "1") (pinfunction "1_1") (pintype "passive"))
      (node (ref "R15") (pin "2") (pinfunction "2_2") (pintype "passive"))
      (node (ref "U5") (pin "6") (pinfunction "-IN_B_6") (pintype "tri_state"))
    )
    (net (code "34") (name "unconnected-(U4-NC-Pad3)") (class "Default")
      (node (ref "U4") (pin "3") (pinfunction "NC_3") (pintype "passive"))
    )
    (net (code "35") (name "unconnected-(U4-NC-Pad9)") (class "Default")
      (node (ref "U4") (pin "9") (pinfunction "NC_9") (pintype "passive"))
    )
    (net (code "36") (name "unconnected-(U6-G1-Pad2)") (class "Default")
      (node (ref "U6") (pin "2") (pinfunction "G1_2") (pintype "passive"))
    )
    (net (code "37") (name "unconnected-(U6-G2-Pad3)") (class "Default")
      (node (ref "U6") (pin "3") (pinfunction "G2_3") (pintype "passive"))
    )
  )
)
